# Power_5V_Boost_Converter.net
KiCad netlist of a schematic drawn in Altium Designer
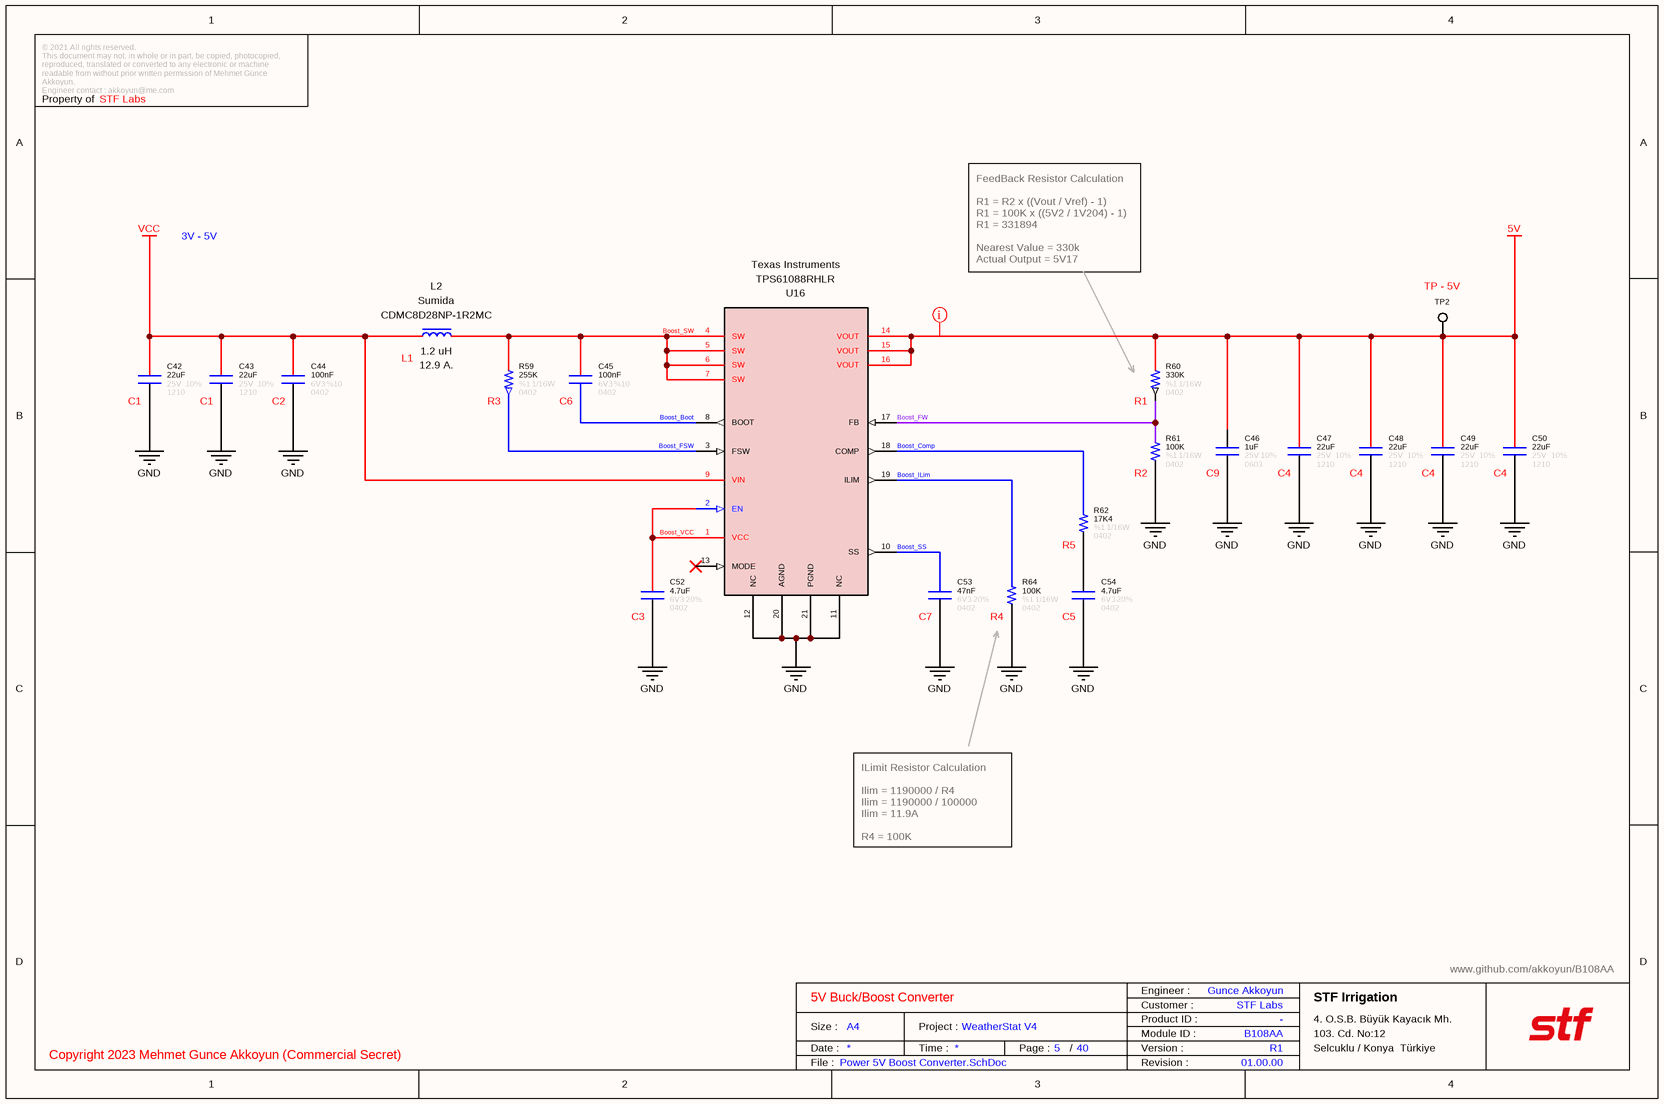
[diagram p0: Power 5V Boost Converter.SchDoc]

(export (version "E")
  (design (tool "Eeschema 10.0.6"))
  (components
    (comp (ref "C42")
      (value "22uF")
      (footprint "CAPACITOR_0603")
      (description "Multilayer Ceramic Capacitors MLCC - SMD/SMT 22UF 25V 10% 1210")
      (fields
        (field (name "MANUFACTURER PART NUMBER") "GRM32ER71E226KE15L")
        (field (name "TOLERANCE") "10%")
        (field (name "CASE") "1210")
        (field (name "VOLTAGE") "25V")
        (field (name "Comment") "Capacitor - 22uF [1210] (Ceramic)")
      )
      (libsource (lib "Akkoyun") (part "Capacitor - 22uF [1210-6V3]"))
    )
    (comp (ref "C43")
      (value "22uF")
      (footprint "CAPACITOR_0603")
      (description "Multilayer Ceramic Capacitors MLCC - SMD/SMT 22UF 25V 10% 1210")
      (fields
        (field (name "MANUFACTURER PART NUMBER") "GRM32ER71E226KE15L")
        (field (name "TOLERANCE") "10%")
        (field (name "CASE") "1210")
        (field (name "VOLTAGE") "25V")
        (field (name "Comment") "Capacitor - 22uF [1210] (Ceramic)")
      )
      (libsource (lib "Akkoyun") (part "Capacitor - 22uF [1210-6V3]"))
    )
    (comp (ref "C44")
      (value "100nF")
      (footprint "CAPACITOR_0402")
      (description "Capacitor - 100nF [0402-6V3] (Ceramic)")
      (fields
        (field (name "MANUFACTURER PART NUMBER") "04026D104KAT4A")
        (field (name "TOLERANCE") "%10")
        (field (name "VOLTAGE") "6V3")
        (field (name "CASE") "0402")
        (field (name "Comment") "Capacitor - 100nF [0402] (Ceramic)")
      )
      (libsource (lib "Akkoyun") (part "Capacitor - 100nF [0402-6V3]"))
    )
    (comp (ref "C45")
      (value "100nF")
      (footprint "CAPACITOR_0402")
      (description "Capacitor - 100nF [0402-6V3] (Ceramic)")
      (fields
        (field (name "MANUFACTURER PART NUMBER") "04026D104KAT4A")
        (field (name "TOLERANCE") "%10")
        (field (name "VOLTAGE") "6V3")
        (field (name "CASE") "0402")
        (field (name "Comment") "Capacitor - 100nF [0402] (Ceramic)")
      )
      (libsource (lib "Akkoyun") (part "Capacitor - 100nF [0402-6V3]"))
    )
    (comp (ref "C46")
      (value "1uF")
      (footprint "CAPACITOR_0603")
      (description "Multilayer Ceramic Capacitors - SMD - 25V 1uF X7R 0603 10%")
      (fields
        (field (name "MANUFACTURER PART NUMBER") "GCJ188R71E105KA01D")
        (field (name "TOLERANCE") "10%")
        (field (name "CASE") "0603")
        (field (name "VOLTAGE") "25V")
        (field (name "Comment") "Capacitor - 1uF [0603] (Ceramic)")
      )
      (libsource (lib "Akkoyun") (part "Capacitor - 1uF [0603-25V]"))
    )
    (comp (ref "C47")
      (value "22uF")
      (footprint "CAPACITOR_0603")
      (description "Multilayer Ceramic Capacitors MLCC - SMD/SMT 22UF 25V 10% 1210")
      (fields
        (field (name "MANUFACTURER PART NUMBER") "GRM32ER71E226KE15L")
        (field (name "TOLERANCE") "10%")
        (field (name "CASE") "1210")
        (field (name "VOLTAGE") "25V")
        (field (name "Comment") "Capacitor - 22uF [1210] (Ceramic)")
      )
      (libsource (lib "Akkoyun") (part "Capacitor - 22uF [1210-6V3]"))
    )
    (comp (ref "C48")
      (value "22uF")
      (footprint "CAPACITOR_0603")
      (description "Multilayer Ceramic Capacitors MLCC - SMD/SMT 22UF 25V 10% 1210")
      (fields
        (field (name "MANUFACTURER PART NUMBER") "GRM32ER71E226KE15L")
        (field (name "TOLERANCE") "10%")
        (field (name "CASE") "1210")
        (field (name "VOLTAGE") "25V")
        (field (name "Comment") "Capacitor - 22uF [1210] (Ceramic)")
      )
      (libsource (lib "Akkoyun") (part "Capacitor - 22uF [1210-6V3]"))
    )
    (comp (ref "C49")
      (value "22uF")
      (footprint "CAPACITOR_0603")
      (description "Multilayer Ceramic Capacitors MLCC - SMD/SMT 22UF 25V 10% 1210")
      (fields
        (field (name "MANUFACTURER PART NUMBER") "GRM32ER71E226KE15L")
        (field (name "TOLERANCE") "10%")
        (field (name "CASE") "1210")
        (field (name "VOLTAGE") "25V")
        (field (name "Comment") "Capacitor - 22uF [1210] (Ceramic)")
      )
      (libsource (lib "Akkoyun") (part "Capacitor - 22uF [1210-6V3]"))
    )
    (comp (ref "C50")
      (value "22uF")
      (footprint "CAPACITOR_0603")
      (description "Multilayer Ceramic Capacitors MLCC - SMD/SMT 22UF 25V 10% 1210")
      (fields
        (field (name "MANUFACTURER PART NUMBER") "GRM32ER71E226KE15L")
        (field (name "TOLERANCE") "10%")
        (field (name "CASE") "1210")
        (field (name "VOLTAGE") "25V")
        (field (name "Comment") "Capacitor - 22uF [1210] (Ceramic)")
      )
      (libsource (lib "Akkoyun") (part "Capacitor - 22uF [1210-6V3]"))
    )
    (comp (ref "C52")
      (value "4.7uF")
      (footprint "CAPACITOR_0402")
      (description "Multilayer Ceramic Capacitors - SMD - 6V3 4.7uF X5R 0402 20%")
      (fields
        (field (name "MANUFACTURER PART NUMBER") "C0402C475M9PACTU")
        (field (name "TOLERANCE") "20%")
        (field (name "CASE") "0402")
        (field (name "VOLTAGE") "6V3")
        (field (name "Comment") "Capacitor - 4.7uF [0402] (Ceramic)")
      )
      (libsource (lib "Akkoyun") (part "Capacitor - 4.7uF [0402-6V3]"))
    )
    (comp (ref "C53")
      (value "47nF")
      (footprint "CAPACITOR_0402")
      (description "Multilayer Ceramic Capacitors - SMD - 6.3V 47nF X7R 0402 10%")
      (fields
        (field (name "MANUFACTURER PART NUMBER") "04026C472MAT2A")
        (field (name "TOLERANCE") "20%")
        (field (name "CASE") "0402")
        (field (name "VOLTAGE") "6V3")
        (field (name "Comment") "Capacitor - 47nF [0402] (Ceramic)")
      )
      (libsource (lib "Akkoyun") (part "Capacitor - 47nF [0402-6V3]"))
    )
    (comp (ref "C54")
      (value "4.7uF")
      (footprint "CAPACITOR_0402")
      (description "Multilayer Ceramic Capacitors - SMD - 6V3 4.7uF X5R 0402 20%")
      (fields
        (field (name "MANUFACTURER PART NUMBER") "C0402C475M9PACTU")
        (field (name "TOLERANCE") "20%")
        (field (name "CASE") "0402")
        (field (name "VOLTAGE") "6V3")
        (field (name "Comment") "Capacitor - 4.7uF [0402] (Ceramic)")
      )
      (libsource (lib "Akkoyun") (part "Capacitor - 4.7uF [0402-6V3]"))
    )
    (comp (ref "L2")
      (value "1.2 uH")
      (footprint "SRP4020TA")
      (description "Power Inductors - SMD SMD Power Inductor 1.2UH 12.9A")
      (fields
        (field (name "TOLERANCE") "20%")
        (field (name "MANUFACTURER NAME") "Sumida")
        (field (name "MANUFACTURER PART NUMBER") "CDMC8D28NP-1R2MC")
        (field (name "MAXIMUM DC CURRENT") "12.9 A.")
        (field (name "Comment") "CDMC8D28NP-1R2MC")
      )
      (libsource (lib "Akkoyun") (part "Inductor - CDMC8D28NP-1R2MC"))
    )
    (comp (ref "R59")
      (value "255K")
      (footprint "RESISTOR_0402")
      (description "Thick Film Resistors - SMD 1/16 W 255 KOhm 1%")
      (fields
        (field (name "MANUFACTURER PART NUMBER") "CRCW0402255KFKED")
        (field (name "POWER") "1/16W")
        (field (name "CASE") "0402")
        (field (name "TOLERANCE") "%1")
        (field (name "Comment") "255K - 0402 - %1 - 1/16W")
      )
      (libsource (lib "Akkoyun") (part "Resistor - 255K [0402]"))
    )
    (comp (ref "R60")
      (value "330K")
      (footprint "RESISTOR_0402")
      (description "Thick Film Resistors - SMD 1/16 W 330 KOhm 1%")
      (fields
        (field (name "MANUFACTURER PART NUMBER") "CRCW0402330KFKED")
        (field (name "TOLERANCE") "%1")
        (field (name "CASE") "0402")
        (field (name "POWER") "1/16W")
        (field (name "Comment") "330K - 0402 - %1 - 1/16W")
      )
      (libsource (lib "Akkoyun") (part "Resistor - 330K [0402]"))
    )
    (comp (ref "R61")
      (value "100K")
      (footprint "RESISTOR_0402")
      (description "Thick Film Resistors - SMD 1/16 W 100 KOhm 1%")
      (fields
        (field (name "MANUFACTURER PART NUMBER") "CRCW0402100KFKED")
        (field (name "TOLERANCE") "%1")
        (field (name "CASE") "0402")
        (field (name "POWER") "1/16W")
        (field (name "Comment") "100K - 0402 - %1 - 1/16W")
      )
      (libsource (lib "Akkoyun") (part "Resistor - 100K [0402]"))
    )
    (comp (ref "R62")
      (value "17K4")
      (footprint "RESISTOR_0402")
      (description "Thick Film Resistors - SMD 1/16 W 17.4 KOhm 1%")
      (fields
        (field (name "MANUFACTURER PART NUMBER") "CRCW040217K4FKED")
        (field (name "TOLERANCE") "%1")
        (field (name "CASE") "0402")
        (field (name "POWER") "1/16W")
        (field (name "Comment") "17K4 - 0402 - %1 - 1/16W")
      )
      (libsource (lib "Akkoyun") (part "Resistor - 17K4 [0402]"))
    )
    (comp (ref "R64")
      (value "100K")
      (footprint "RESISTOR_0402")
      (description "Thick Film Resistors - SMD 1/16 W 100 KOhm 1%")
      (fields
        (field (name "MANUFACTURER PART NUMBER") "CRCW0402100KFKED")
        (field (name "TOLERANCE") "%1")
        (field (name "CASE") "0402")
        (field (name "POWER") "1/16W")
        (field (name "Comment") "100K - 0402 - %1 - 1/16W")
      )
      (libsource (lib "Akkoyun") (part "Resistor - 100K [0402]"))
    )
    (comp (ref "TP2")
      (value "TP - 5V")
      (footprint "TP")
      (description "Test Point")
      (libsource (lib "Akkoyun") (part "PCB - Test Point"))
    )
    (comp (ref "U16")
      (value "TPS61088RHLR")
      (footprint "VQFN-20")
      (description "Switching Voltage Regulators 10-A Fully-Integrated Synchronous Boost Converter 20-VQFN -40 to 85")
      (fields
        (field (name "MANUFACTURER PART NUMBER") "TPS61088RHLR")
        (field (name "MANUFACTURER NAME") "Texas Instruments")
      )
      (libsource (lib "Akkoyun") (part "IC - TPS61088"))
    )
  )
  (nets
    (net (code "1") (name "/Boost_Boot") (class "Default")
      (node (ref "C45") (pin "1") (pinfunction "1_1") (pintype "passive"))
      (node (ref "U16") (pin "8") (pinfunction "BOOT_8") (pintype "output"))
    )
    (net (code "2") (name "/Boost_Comp") (class "Default")
      (node (ref "R62") (pin "2") (pinfunction "2_2") (pintype "passive"))
      (node (ref "U16") (pin "18") (pinfunction "COMP_18") (pintype "output"))
    )
    (net (code "3") (name "/Boost_FSW") (class "Default")
      (node (ref "R59") (pin "1") (pinfunction "1_1") (pintype "output"))
      (node (ref "U16") (pin "3") (pinfunction "FSW_3") (pintype "input"))
    )
    (net (code "4") (name "/Boost_FW") (class "Default")
      (node (ref "R60") (pin "1") (pinfunction "1_1") (pintype "output"))
      (node (ref "R61") (pin "2") (pinfunction "2_2") (pintype "passive"))
      (node (ref "U16") (pin "17") (pinfunction "FB_17") (pintype "input"))
    )
    (net (code "5") (name "/Boost_ILim") (class "Default")
      (node (ref "R64") (pin "2") (pinfunction "2_2") (pintype "passive"))
      (node (ref "U16") (pin "19") (pinfunction "ILIM_19") (pintype "output"))
    )
    (net (code "6") (name "/Boost_SS") (class "Default")
      (node (ref "C53") (pin "2") (pinfunction "2_2") (pintype "passive"))
      (node (ref "U16") (pin "10") (pinfunction "SS_10") (pintype "output"))
    )
    (net (code "7") (name "/Boost_SW") (class "Default")
      (node (ref "C45") (pin "2") (pinfunction "2_2") (pintype "passive"))
      (node (ref "L2") (pin "2") (pinfunction "2_2") (pintype "passive"))
      (node (ref "R59") (pin "2") (pinfunction "2_2") (pintype "passive"))
      (node (ref "U16") (pin "4") (pinfunction "SW_4") (pintype "power_in"))
      (node (ref "U16") (pin "5") (pinfunction "SW_5") (pintype "power_in"))
      (node (ref "U16") (pin "6") (pinfunction "SW_6") (pintype "power_in"))
      (node (ref "U16") (pin "7") (pinfunction "SW_7") (pintype "power_in"))
    )
    (net (code "8") (name "/Boost_VCC") (class "Default")
      (node (ref "C52") (pin "2") (pinfunction "2_2") (pintype "passive"))
      (node (ref "U16") (pin "1") (pinfunction "VCC_1") (pintype "power_in"))
      (node (ref "U16") (pin "2") (pinfunction "EN_2") (pintype "input"))
    )
    (net (code "9") (name "5V") (class "Default")
      (node (ref "C46") (pin "2") (pinfunction "2_2") (pintype "passive"))
      (node (ref "C47") (pin "2") (pinfunction "2_2") (pintype "passive"))
      (node (ref "C48") (pin "2") (pinfunction "2_2") (pintype "passive"))
      (node (ref "C49") (pin "2") (pinfunction "2_2") (pintype "passive"))
      (node (ref "C50") (pin "2") (pinfunction "2_2") (pintype "passive"))
      (node (ref "R60") (pin "2") (pinfunction "2_2") (pintype "passive"))
      (node (ref "TP2") (pin "1") (pinfunction "1_1") (pintype "passive"))
      (node (ref "U16") (pin "14") (pinfunction "VOUT_14") (pintype "power_in"))
      (node (ref "U16") (pin "15") (pinfunction "VOUT_15") (pintype "power_in"))
      (node (ref "U16") (pin "16") (pinfunction "VOUT_16") (pintype "power_in"))
    )
    (net (code "10") (name "GND") (class "Default")
      (node (ref "C42") (pin "1") (pinfunction "1_1") (pintype "passive"))
      (node (ref "C43") (pin "1") (pinfunction "1_1") (pintype "passive"))
      (node (ref "C44") (pin "1") (pinfunction "1_1") (pintype "passive"))
      (node (ref "C46") (pin "1") (pinfunction "1_1") (pintype "passive"))
      (node (ref "C47") (pin "1") (pinfunction "1_1") (pintype "passive"))
      (node (ref "C48") (pin "1") (pinfunction "1_1") (pintype "passive"))
      (node (ref "C49") (pin "1") (pinfunction "1_1") (pintype "passive"))
      (node (ref "C50") (pin "1") (pinfunction "1_1") (pintype "passive"))
      (node (ref "C52") (pin "1") (pinfunction "1_1") (pintype "passive"))
      (node (ref "C53") (pin "1") (pinfunction "1_1") (pintype "passive"))
      (node (ref "C54") (pin "1") (pinfunction "1_1") (pintype "passive"))
      (node (ref "R61") (pin "1") (pinfunction "1_1") (pintype "passive"))
      (node (ref "R64") (pin "1") (pinfunction "1_1") (pintype "passive"))
      (node (ref "U16") (pin "11") (pinfunction "NC_11") (pintype "passive"))
      (node (ref "U16") (pin "12") (pinfunction "NC_12") (pintype "passive"))
      (node (ref "U16") (pin "20") (pinfunction "AGND_20") (pintype "power_in"))
      (node (ref "U16") (pin "21") (pinfunction "PGND_21") (pintype "power_in"))
    )
    (net (code "11") (name "Net-(C54-Pad2)") (class "Default")
      (node (ref "C54") (pin "2") (pinfunction "2_2") (pintype "passive"))
      (node (ref "R62") (pin "1") (pinfunction "1_1") (pintype "passive"))
    )
    (net (code "12") (name "VCC") (class "Default")
      (node (ref "C42") (pin "2") (pinfunction "2_2") (pintype "passive"))
      (node (ref "C43") (pin "2") (pinfunction "2_2") (pintype "passive"))
      (node (ref "C44") (pin "2") (pinfunction "2_2") (pintype "passive"))
      (node (ref "L2") (pin "1") (pinfunction "1_1") (pintype "passive"))
      (node (ref "U16") (pin "9") (pinfunction "VIN_9") (pintype "power_in"))
    )
    (net (code "13") (name "unconnected-(U16-MODE-Pad13)") (class "Default")
      (node (ref "U16") (pin "13") (pinfunction "MODE_13") (pintype "input+no_connect"))
    )
  )
)
